# Adafruit_VL6180X.net
KiCad netlist of a schematic drawn in EAGLE
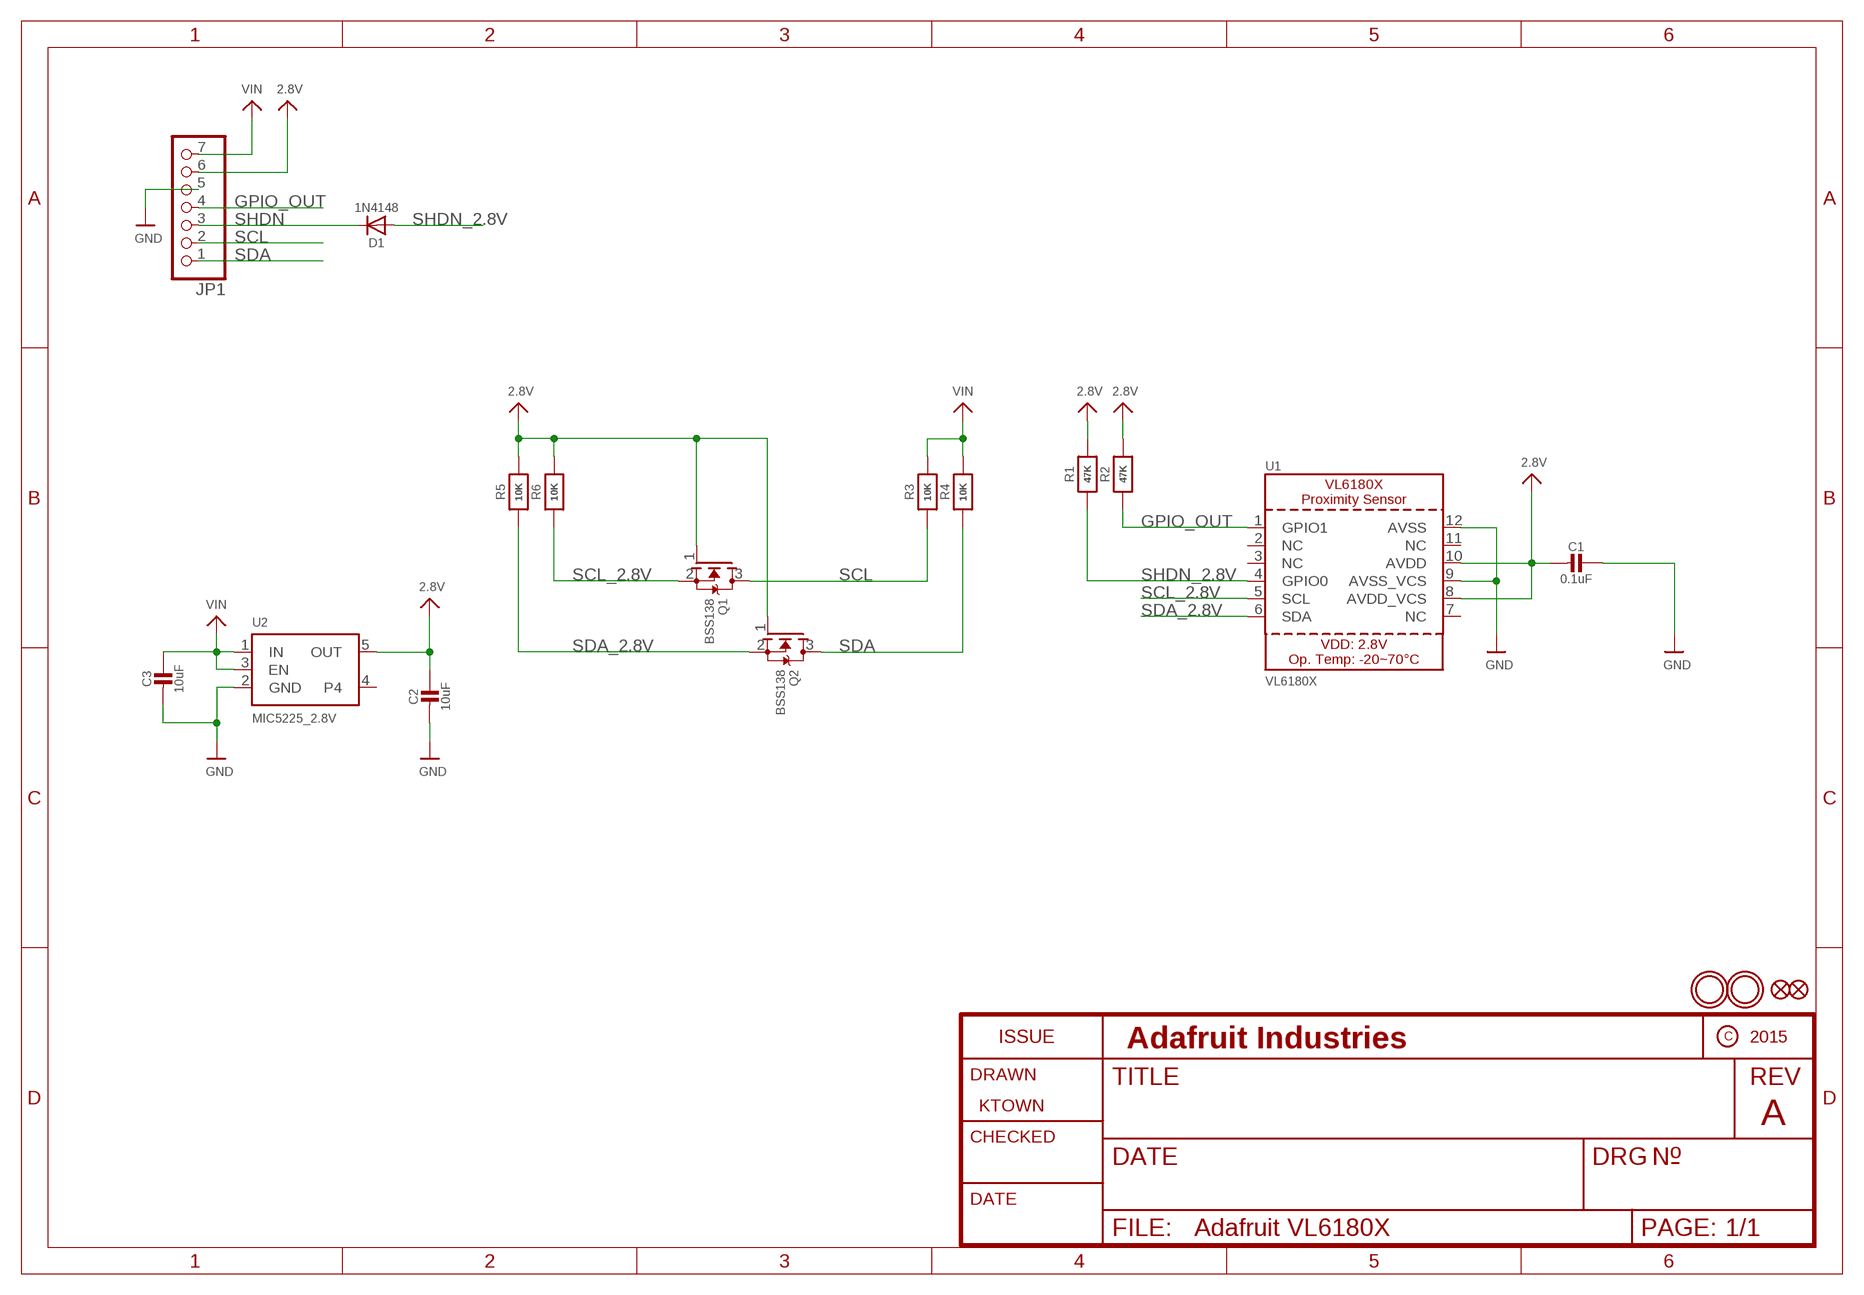
[diagram p0: schematic, sheet 1]

(export (version "E")
  (design (tool "Eeschema 10.0.6"))
  (components
    (comp (ref "C1")
      (value "0.1uF")
      (footprint "eagle-import:0805-NO")
      (libsource (lib "eagle-import") (part "CAP_CERAMIC0805-NOOUTLINE"))
    )
    (comp (ref "C2")
      (value "10uF")
      (footprint "eagle-import:0805-NO")
      (libsource (lib "eagle-import") (part "CAP_CERAMIC0805-NOOUTLINE"))
    )
    (comp (ref "C3")
      (value "10uF")
      (footprint "eagle-import:0805-NO")
      (libsource (lib "eagle-import") (part "CAP_CERAMIC0805-NOOUTLINE"))
    )
    (comp (ref "D1")
      (value "1N4148")
      (footprint "eagle-import:SOD-323")
      (libsource (lib "eagle-import") (part "DIODESOD-323"))
    )
    (comp (ref "FID1")
      (value "FIDUCIAL\"\"")
      (footprint "eagle-import:FIDUCIAL_1MM")
      (libsource (lib "eagle-import") (part "FIDUCIAL{dblquote}{dblquote}"))
    )
    (comp (ref "FID2")
      (value "FIDUCIAL\"\"")
      (footprint "eagle-import:FIDUCIAL_1MM")
      (libsource (lib "eagle-import") (part "FIDUCIAL{dblquote}{dblquote}"))
    )
    (comp (ref "JP1")
      (value "HEADER-1X770MIL")
      (footprint "eagle-import:1X07_ROUND_70")
      (libsource (lib "eagle-import") (part "HEADER-1X770MIL"))
    )
    (comp (ref "Q1")
      (value "BSS138")
      (footprint "eagle-import:SOT23-WIDE")
      (libsource (lib "eagle-import") (part "MOSFET-NWIDE"))
    )
    (comp (ref "Q2")
      (value "BSS138")
      (footprint "eagle-import:SOT23-WIDE")
      (libsource (lib "eagle-import") (part "MOSFET-NWIDE"))
    )
    (comp (ref "R1")
      (value "47K")
      (footprint "eagle-import:0805-NO")
      (libsource (lib "eagle-import") (part "RESISTOR0805_NOOUTLINE"))
    )
    (comp (ref "R2")
      (value "47K")
      (footprint "eagle-import:0805-NO")
      (libsource (lib "eagle-import") (part "RESISTOR0805_NOOUTLINE"))
    )
    (comp (ref "R3")
      (value "10K")
      (footprint "eagle-import:0805-NO")
      (libsource (lib "eagle-import") (part "RESISTOR0805_NOOUTLINE"))
    )
    (comp (ref "R4")
      (value "10K")
      (footprint "eagle-import:0805-NO")
      (libsource (lib "eagle-import") (part "RESISTOR0805_NOOUTLINE"))
    )
    (comp (ref "R5")
      (value "10K")
      (footprint "eagle-import:0805-NO")
      (libsource (lib "eagle-import") (part "RESISTOR0805_NOOUTLINE"))
    )
    (comp (ref "R6")
      (value "10K")
      (footprint "eagle-import:0805-NO")
      (libsource (lib "eagle-import") (part "RESISTOR0805_NOOUTLINE"))
    )
    (comp (ref "U$11")
      (value "MOUNTINGHOLE2.5")
      (footprint "eagle-import:MOUNTINGHOLE_2.5_PLATED")
      (libsource (lib "eagle-import") (part "MOUNTINGHOLE2.5"))
    )
    (comp (ref "U$12")
      (value "MOUNTINGHOLE2.5")
      (footprint "eagle-import:MOUNTINGHOLE_2.5_PLATED")
      (libsource (lib "eagle-import") (part "MOUNTINGHOLE2.5"))
    )
    (comp (ref "U1")
      (value "VL6180X")
      (footprint "eagle-import:VL6180")
      (libsource (lib "eagle-import") (part "VL6180X"))
    )
    (comp (ref "U2")
      (value "MIC5225_2.8V")
      (footprint "eagle-import:SOT23-5")
      (libsource (lib "eagle-import") (part "VREG_SOT23-5"))
    )
  )
  (nets
    (net (code "1") (name "/GPIO_OUT") (class "Default")
      (node (ref "JP1") (pin "4") (pinfunction "4_4") (pintype "passive"))
      (node (ref "R2") (pin "1") (pinfunction "1_1") (pintype "passive"))
      (node (ref "U1") (pin "1") (pinfunction "GPIO1_1") (pintype "bidirectional"))
    )
    (net (code "2") (name "/SCL") (class "Default")
      (node (ref "JP1") (pin "2") (pinfunction "2_2") (pintype "passive"))
      (node (ref "Q1") (pin "3") (pinfunction "D_3") (pintype "bidirectional"))
      (node (ref "R3") (pin "1") (pinfunction "1_1") (pintype "passive"))
    )
    (net (code "3") (name "/SCL_2.8V") (class "Default")
      (node (ref "Q1") (pin "2") (pinfunction "S_2") (pintype "bidirectional"))
      (node (ref "R6") (pin "1") (pinfunction "1_1") (pintype "passive"))
      (node (ref "U1") (pin "5") (pinfunction "SCL_5") (pintype "input"))
    )
    (net (code "4") (name "/SDA") (class "Default")
      (node (ref "JP1") (pin "1") (pinfunction "1_1") (pintype "passive"))
      (node (ref "Q2") (pin "3") (pinfunction "D_3") (pintype "bidirectional"))
      (node (ref "R4") (pin "1") (pinfunction "1_1") (pintype "passive"))
    )
    (net (code "5") (name "/SDA_2.8V") (class "Default")
      (node (ref "Q2") (pin "2") (pinfunction "S_2") (pintype "bidirectional"))
      (node (ref "R5") (pin "1") (pinfunction "1_1") (pintype "passive"))
      (node (ref "U1") (pin "6") (pinfunction "SDA_6") (pintype "bidirectional"))
    )
    (net (code "6") (name "/SHDN") (class "Default")
      (node (ref "D1") (pin "C") (pinfunction "C_C") (pintype "passive"))
      (node (ref "JP1") (pin "3") (pinfunction "3_3") (pintype "passive"))
    )
    (net (code "7") (name "/SHDN_2.8V") (class "Default")
      (node (ref "D1") (pin "A") (pinfunction "A_A") (pintype "passive"))
      (node (ref "R1") (pin "1") (pinfunction "1_1") (pintype "passive"))
      (node (ref "U1") (pin "4") (pinfunction "GPIO0_4") (pintype "bidirectional"))
    )
    (net (code "8") (name "2.8V") (class "Default")
      (node (ref "C1") (pin "2") (pinfunction "2_2") (pintype "passive"))
      (node (ref "C2") (pin "1") (pinfunction "1_1") (pintype "passive"))
      (node (ref "JP1") (pin "6") (pinfunction "6_6") (pintype "passive"))
      (node (ref "Q1") (pin "1") (pinfunction "G_1") (pintype "bidirectional"))
      (node (ref "Q2") (pin "1") (pinfunction "G_1") (pintype "bidirectional"))
      (node (ref "R1") (pin "2") (pinfunction "2_2") (pintype "passive"))
      (node (ref "R2") (pin "2") (pinfunction "2_2") (pintype "passive"))
      (node (ref "R5") (pin "2") (pinfunction "2_2") (pintype "passive"))
      (node (ref "R6") (pin "2") (pinfunction "2_2") (pintype "passive"))
      (node (ref "U1") (pin "10") (pinfunction "AVDD_10") (pintype "power_in"))
      (node (ref "U1") (pin "8") (pinfunction "AVDD_VCS_8") (pintype "power_in"))
      (node (ref "U2") (pin "5") (pinfunction "OUT_5") (pintype "power_in"))
    )
    (net (code "9") (name "GND") (class "Default")
      (node (ref "C1") (pin "1") (pinfunction "1_1") (pintype "passive"))
      (node (ref "C2") (pin "2") (pinfunction "2_2") (pintype "passive"))
      (node (ref "C3") (pin "2") (pinfunction "2_2") (pintype "passive"))
      (node (ref "JP1") (pin "5") (pinfunction "5_5") (pintype "passive"))
      (node (ref "U1") (pin "12") (pinfunction "AVSS_12") (pintype "power_in"))
      (node (ref "U1") (pin "9") (pinfunction "AVSS_VCS_9") (pintype "power_in"))
      (node (ref "U2") (pin "2") (pinfunction "GND_2") (pintype "power_in"))
    )
    (net (code "10") (name "VIN") (class "Default")
      (node (ref "C3") (pin "1") (pinfunction "1_1") (pintype "passive"))
      (node (ref "JP1") (pin "7") (pinfunction "7_7") (pintype "passive"))
      (node (ref "R3") (pin "2") (pinfunction "2_2") (pintype "passive"))
      (node (ref "R4") (pin "2") (pinfunction "2_2") (pintype "passive"))
      (node (ref "U2") (pin "1") (pinfunction "IN_1") (pintype "power_in"))
      (node (ref "U2") (pin "3") (pinfunction "EN_3") (pintype "input"))
    )
    (net (code "11") (name "unconnected-(U1-NC-Pad2)") (class "Default")
      (node (ref "U1") (pin "2") (pinfunction "NC_2") (pintype "no_connect"))
    )
    (net (code "12") (name "unconnected-(U1-NC-Pad3)") (class "Default")
      (node (ref "U1") (pin "3") (pinfunction "NC_3") (pintype "no_connect"))
    )
    (net (code "13") (name "unconnected-(U1-NC-Pad7)") (class "Default")
      (node (ref "U1") (pin "7") (pinfunction "NC_7") (pintype "no_connect"))
    )
    (net (code "14") (name "unconnected-(U1-NC-Pad11)") (class "Default")
      (node (ref "U1") (pin "11") (pinfunction "NC_11") (pintype "no_connect"))
    )
    (net (code "15") (name "unconnected-(U2-P4-Pad4)") (class "Default")
      (node (ref "U2") (pin "4") (pinfunction "P4_4") (pintype "bidirectional"))
    )
  )
)
